# LED.net
KiCad netlist of a schematic drawn in Altium Designer
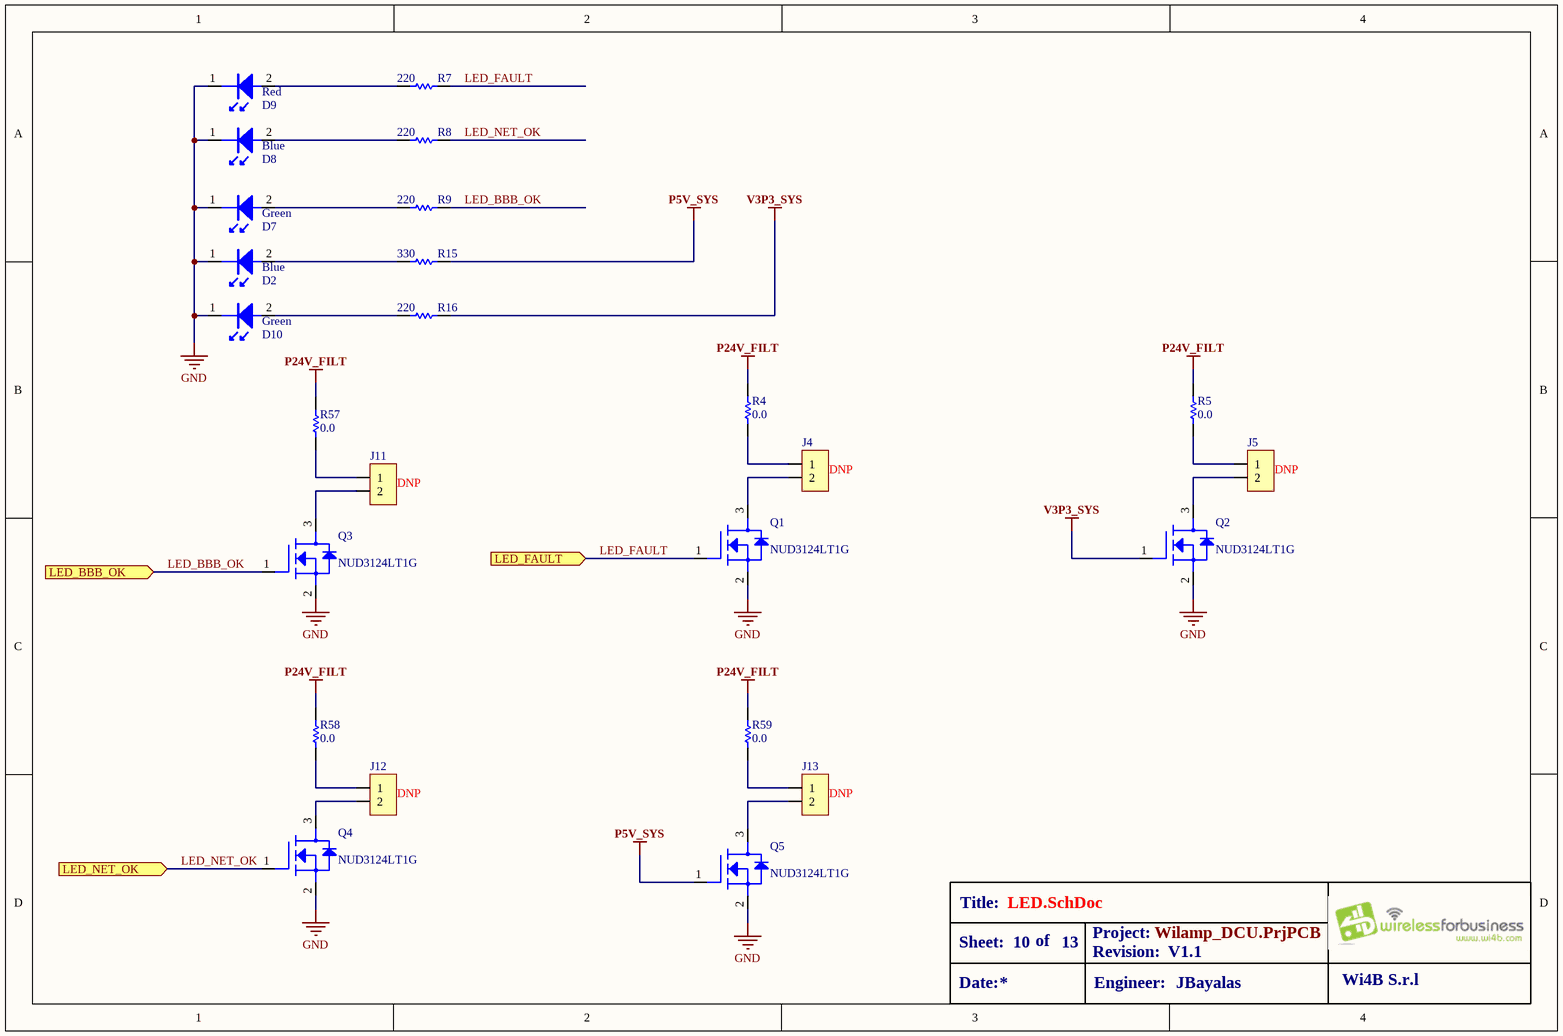
[diagram p0: LED.SchDoc]

(export (version "E")
  (design (tool "Eeschema 10.0.6"))
  (components
    (comp (ref "D2")
      (value "Blue")
      (footprint "LED0402(BLUE)")
      (description "LED BLUE 0402 SMD")
      (fields (field (name "MPN") "VLMB1500-GS08"))
      (libsource (lib "Diode") (part "VLMB1500-GS08"))
    )
    (comp (ref "D7")
      (value "Green")
      (footprint "LED0402(GREEN)")
      (description "LED GREEN 0402 SMD")
      (fields (field (name "MPN") "LNJ347W83RA"))
      (libsource (lib "Diode") (part "LNJ347W83RA"))
    )
    (comp (ref "D8")
      (value "Blue")
      (footprint "LED0402(BLUE)")
      (description "LED BLUE 0402 SMD")
      (fields (field (name "MPN") "VLMB1500-GS08"))
      (libsource (lib "Diode") (part "VLMB1500-GS08"))
    )
    (comp (ref "D9")
      (value "Red")
      (footprint "LED0402(RED)")
      (description "LED RED 0402 SMD")
      (fields (field (name "MPN") "LNJ247W82RA"))
      (libsource (lib "Diode") (part "LNJ247W82RA"))
    )
    (comp (ref "D10")
      (value "Green")
      (footprint "LED0402(GREEN)")
      (description "LED GREEN 0402 SMD")
      (fields (field (name "MPN") "LNJ347W83RA"))
      (libsource (lib "Diode") (part "LNJ347W83RA"))
    )
    (comp (ref "J4")
      (value "*")
      (footprint "2pin 5mm Pitch")
      (fields (field (name "LOAD") "DNP"))
      (libsource (lib "Miscellaneous") (part "2PIN Signal 5mm Pitch"))
    )
    (comp (ref "J5")
      (value "*")
      (footprint "2pin 5mm Pitch")
      (fields (field (name "LOAD") "DNP"))
      (libsource (lib "Miscellaneous") (part "2PIN Signal 5mm Pitch"))
    )
    (comp (ref "J11")
      (value "*")
      (footprint "2pin 5mm Pitch")
      (fields (field (name "LOAD") "DNP"))
      (libsource (lib "Miscellaneous") (part "2PIN Signal 5mm Pitch"))
    )
    (comp (ref "J12")
      (value "*")
      (footprint "2pin 5mm Pitch")
      (fields (field (name "LOAD") "DNP"))
      (libsource (lib "Miscellaneous") (part "2PIN Signal 5mm Pitch"))
    )
    (comp (ref "J13")
      (value "*")
      (footprint "2pin 5mm Pitch")
      (fields (field (name "LOAD") "DNP"))
      (libsource (lib "Miscellaneous") (part "2PIN Signal 5mm Pitch"))
    )
    (comp (ref "Q1")
      (value "*")
      (footprint "SOT-23-3")
      (description "IC INDCT LOAD DRVR AUTO SOT23")
      (fields (field (name "MPN") "NUD3124LT1G"))
      (libsource (lib "Transistor") (part "NUD3124LT1G"))
    )
    (comp (ref "Q2")
      (value "*")
      (footprint "SOT-23-3")
      (description "IC INDCT LOAD DRVR AUTO SOT23")
      (fields (field (name "MPN") "NUD3124LT1G"))
      (libsource (lib "Transistor") (part "NUD3124LT1G"))
    )
    (comp (ref "Q3")
      (value "*")
      (footprint "SOT-23-3")
      (description "IC INDCT LOAD DRVR AUTO SOT23")
      (fields (field (name "MPN") "NUD3124LT1G"))
      (libsource (lib "Transistor") (part "NUD3124LT1G"))
    )
    (comp (ref "Q4")
      (value "*")
      (footprint "SOT-23-3")
      (description "IC INDCT LOAD DRVR AUTO SOT23")
      (fields (field (name "MPN") "NUD3124LT1G"))
      (libsource (lib "Transistor") (part "NUD3124LT1G"))
    )
    (comp (ref "Q5")
      (value "*")
      (footprint "SOT-23-3")
      (description "IC INDCT LOAD DRVR AUTO SOT23")
      (fields (field (name "MPN") "NUD3124LT1G"))
      (libsource (lib "Transistor") (part "NUD3124LT1G"))
    )
    (comp (ref "R4")
      (value "0.0")
      (footprint "R1206")
      (description "RES SMD 0.0 OHM JUMPER 1/4W 1206")
      (fields (field (name "MPN") "RC1206JR-070RL"))
      (libsource (lib "Res") (part "RC1206JR-070RL"))
    )
    (comp (ref "R5")
      (value "0.0")
      (footprint "R1206")
      (description "RES SMD 0.0 OHM JUMPER 1/4W 1206")
      (fields (field (name "MPN") "RC1206JR-070RL"))
      (libsource (lib "Res") (part "RC1206JR-070RL"))
    )
    (comp (ref "R7")
      (value "220")
      (footprint "R0402")
      (description "RES SMD 220 OHM 5% 1/16W 0402")
      (fields (field (name "MPN") "RC0402JR-07220RL"))
      (libsource (lib "Res") (part "RC0402JR-07220RL"))
    )
    (comp (ref "R8")
      (value "220")
      (footprint "R0402")
      (description "RES SMD 220 OHM 5% 1/16W 0402")
      (fields (field (name "MPN") "RC0402JR-07220RL"))
      (libsource (lib "Res") (part "RC0402JR-07220RL"))
    )
    (comp (ref "R9")
      (value "220")
      (footprint "R0402")
      (description "RES SMD 220 OHM 5% 1/16W 0402")
      (fields (field (name "MPN") "RC0402JR-07220RL"))
      (libsource (lib "Res") (part "RC0402JR-07220RL"))
    )
    (comp (ref "R15")
      (value "330")
      (footprint "R0402")
      (description "RES SMD 330 OHM 1% 1/16W 0402")
      (fields (field (name "MPN") "CRCW0402330RFKED"))
      (libsource (lib "Res") (part "CRCW0402330RFKED"))
    )
    (comp (ref "R16")
      (value "220")
      (footprint "R0402")
      (description "RES SMD 220 OHM 5% 1/16W 0402")
      (fields (field (name "MPN") "RC0402JR-07220RL"))
      (libsource (lib "Res") (part "RC0402JR-07220RL"))
    )
    (comp (ref "R57")
      (value "0.0")
      (footprint "R1206")
      (description "RES SMD 0.0 OHM JUMPER 1/4W 1206")
      (fields (field (name "MPN") "RC1206JR-070RL"))
      (libsource (lib "Res") (part "RC1206JR-070RL"))
    )
    (comp (ref "R58")
      (value "0.0")
      (footprint "R1206")
      (description "RES SMD 0.0 OHM JUMPER 1/4W 1206")
      (fields (field (name "MPN") "RC1206JR-070RL"))
      (libsource (lib "Res") (part "RC1206JR-070RL"))
    )
    (comp (ref "R59")
      (value "0.0")
      (footprint "R1206")
      (description "RES SMD 0.0 OHM JUMPER 1/4W 1206")
      (fields (field (name "MPN") "RC1206JR-070RL"))
      (libsource (lib "Res") (part "RC1206JR-070RL"))
    )
  )
  (nets
    (net (code "1") (name "/LED_BBB_OK") (class "Default")
      (node (ref "Q3") (pin "1") (pinfunction "gate_1") (pintype "passive"))
      (node (ref "R9") (pin "2") (pinfunction "2_2") (pintype "passive"))
    )
    (net (code "2") (name "/LED_FAULT") (class "Default")
      (node (ref "Q1") (pin "1") (pinfunction "gate_1") (pintype "passive"))
      (node (ref "R7") (pin "2") (pinfunction "2_2") (pintype "passive"))
    )
    (net (code "3") (name "/LED_NET_OK") (class "Default")
      (node (ref "Q4") (pin "1") (pinfunction "gate_1") (pintype "passive"))
      (node (ref "R8") (pin "2") (pinfunction "2_2") (pintype "passive"))
    )
    (net (code "4") (name "GND") (class "Default")
      (node (ref "D10") (pin "1") (pinfunction "1_1") (pintype "passive"))
      (node (ref "D2") (pin "1") (pinfunction "1_1") (pintype "passive"))
      (node (ref "D7") (pin "1") (pinfunction "1_1") (pintype "passive"))
      (node (ref "D8") (pin "1") (pinfunction "1_1") (pintype "passive"))
      (node (ref "D9") (pin "1") (pinfunction "1_1") (pintype "passive"))
      (node (ref "Q1") (pin "2") (pinfunction "source_2") (pintype "passive"))
      (node (ref "Q2") (pin "2") (pinfunction "source_2") (pintype "passive"))
      (node (ref "Q3") (pin "2") (pinfunction "source_2") (pintype "passive"))
      (node (ref "Q4") (pin "2") (pinfunction "source_2") (pintype "passive"))
      (node (ref "Q5") (pin "2") (pinfunction "source_2") (pintype "passive"))
    )
    (net (code "5") (name "Net-(D2-Pad2)") (class "Default")
      (node (ref "D2") (pin "2") (pinfunction "2_2") (pintype "passive"))
      (node (ref "R15") (pin "1") (pinfunction "1_1") (pintype "passive"))
    )
    (net (code "6") (name "Net-(D7-Pad2)") (class "Default")
      (node (ref "D7") (pin "2") (pinfunction "2_2") (pintype "passive"))
      (node (ref "R9") (pin "1") (pinfunction "1_1") (pintype "passive"))
    )
    (net (code "7") (name "Net-(D8-Pad2)") (class "Default")
      (node (ref "D8") (pin "2") (pinfunction "2_2") (pintype "passive"))
      (node (ref "R8") (pin "1") (pinfunction "1_1") (pintype "passive"))
    )
    (net (code "8") (name "Net-(D9-Pad2)") (class "Default")
      (node (ref "D9") (pin "2") (pinfunction "2_2") (pintype "passive"))
      (node (ref "R7") (pin "1") (pinfunction "1_1") (pintype "passive"))
    )
    (net (code "9") (name "Net-(D10-Pad2)") (class "Default")
      (node (ref "D10") (pin "2") (pinfunction "2_2") (pintype "passive"))
      (node (ref "R16") (pin "1") (pinfunction "1_1") (pintype "passive"))
    )
    (net (code "10") (name "Net-(J4-Pad1)") (class "Default")
      (node (ref "J4") (pin "1") (pinfunction "1_1") (pintype "passive"))
      (node (ref "R4") (pin "1") (pinfunction "1_1") (pintype "passive"))
    )
    (net (code "11") (name "Net-(J5-Pad1)") (class "Default")
      (node (ref "J5") (pin "1") (pinfunction "1_1") (pintype "passive"))
      (node (ref "R5") (pin "1") (pinfunction "1_1") (pintype "passive"))
    )
    (net (code "12") (name "Net-(J11-Pad1)") (class "Default")
      (node (ref "J11") (pin "1") (pinfunction "1_1") (pintype "passive"))
      (node (ref "R57") (pin "1") (pinfunction "1_1") (pintype "passive"))
    )
    (net (code "13") (name "Net-(J12-Pad1)") (class "Default")
      (node (ref "J12") (pin "1") (pinfunction "1_1") (pintype "passive"))
      (node (ref "R58") (pin "1") (pinfunction "1_1") (pintype "passive"))
    )
    (net (code "14") (name "Net-(J13-Pad1)") (class "Default")
      (node (ref "J13") (pin "1") (pinfunction "1_1") (pintype "passive"))
      (node (ref "R59") (pin "1") (pinfunction "1_1") (pintype "passive"))
    )
    (net (code "15") (name "Net-(Q1-drain)") (class "Default")
      (node (ref "J4") (pin "2") (pinfunction "2_2") (pintype "passive"))
      (node (ref "Q1") (pin "3") (pinfunction "drain_3") (pintype "passive"))
    )
    (net (code "16") (name "Net-(Q2-drain)") (class "Default")
      (node (ref "J5") (pin "2") (pinfunction "2_2") (pintype "passive"))
      (node (ref "Q2") (pin "3") (pinfunction "drain_3") (pintype "passive"))
    )
    (net (code "17") (name "Net-(Q3-drain)") (class "Default")
      (node (ref "J11") (pin "2") (pinfunction "2_2") (pintype "passive"))
      (node (ref "Q3") (pin "3") (pinfunction "drain_3") (pintype "passive"))
    )
    (net (code "18") (name "Net-(Q4-drain)") (class "Default")
      (node (ref "J12") (pin "2") (pinfunction "2_2") (pintype "passive"))
      (node (ref "Q4") (pin "3") (pinfunction "drain_3") (pintype "passive"))
    )
    (net (code "19") (name "Net-(Q5-drain)") (class "Default")
      (node (ref "J13") (pin "2") (pinfunction "2_2") (pintype "passive"))
      (node (ref "Q5") (pin "3") (pinfunction "drain_3") (pintype "passive"))
    )
    (net (code "20") (name "P5V_SYS") (class "Default")
      (node (ref "Q5") (pin "1") (pinfunction "gate_1") (pintype "passive"))
      (node (ref "R15") (pin "2") (pinfunction "2_2") (pintype "passive"))
    )
    (net (code "21") (name "P24V_FILT") (class "Default")
      (node (ref "R4") (pin "2") (pinfunction "2_2") (pintype "passive"))
      (node (ref "R5") (pin "2") (pinfunction "2_2") (pintype "passive"))
      (node (ref "R57") (pin "2") (pinfunction "2_2") (pintype "passive"))
      (node (ref "R58") (pin "2") (pinfunction "2_2") (pintype "passive"))
      (node (ref "R59") (pin "2") (pinfunction "2_2") (pintype "passive"))
    )
    (net (code "22") (name "V3P3_SYS") (class "Default")
      (node (ref "Q2") (pin "1") (pinfunction "gate_1") (pintype "passive"))
      (node (ref "R16") (pin "2") (pinfunction "2_2") (pintype "passive"))
    )
  )
)
